# Optical_Encoder_10-17-16.net
KiCad netlist of a schematic drawn in EAGLE
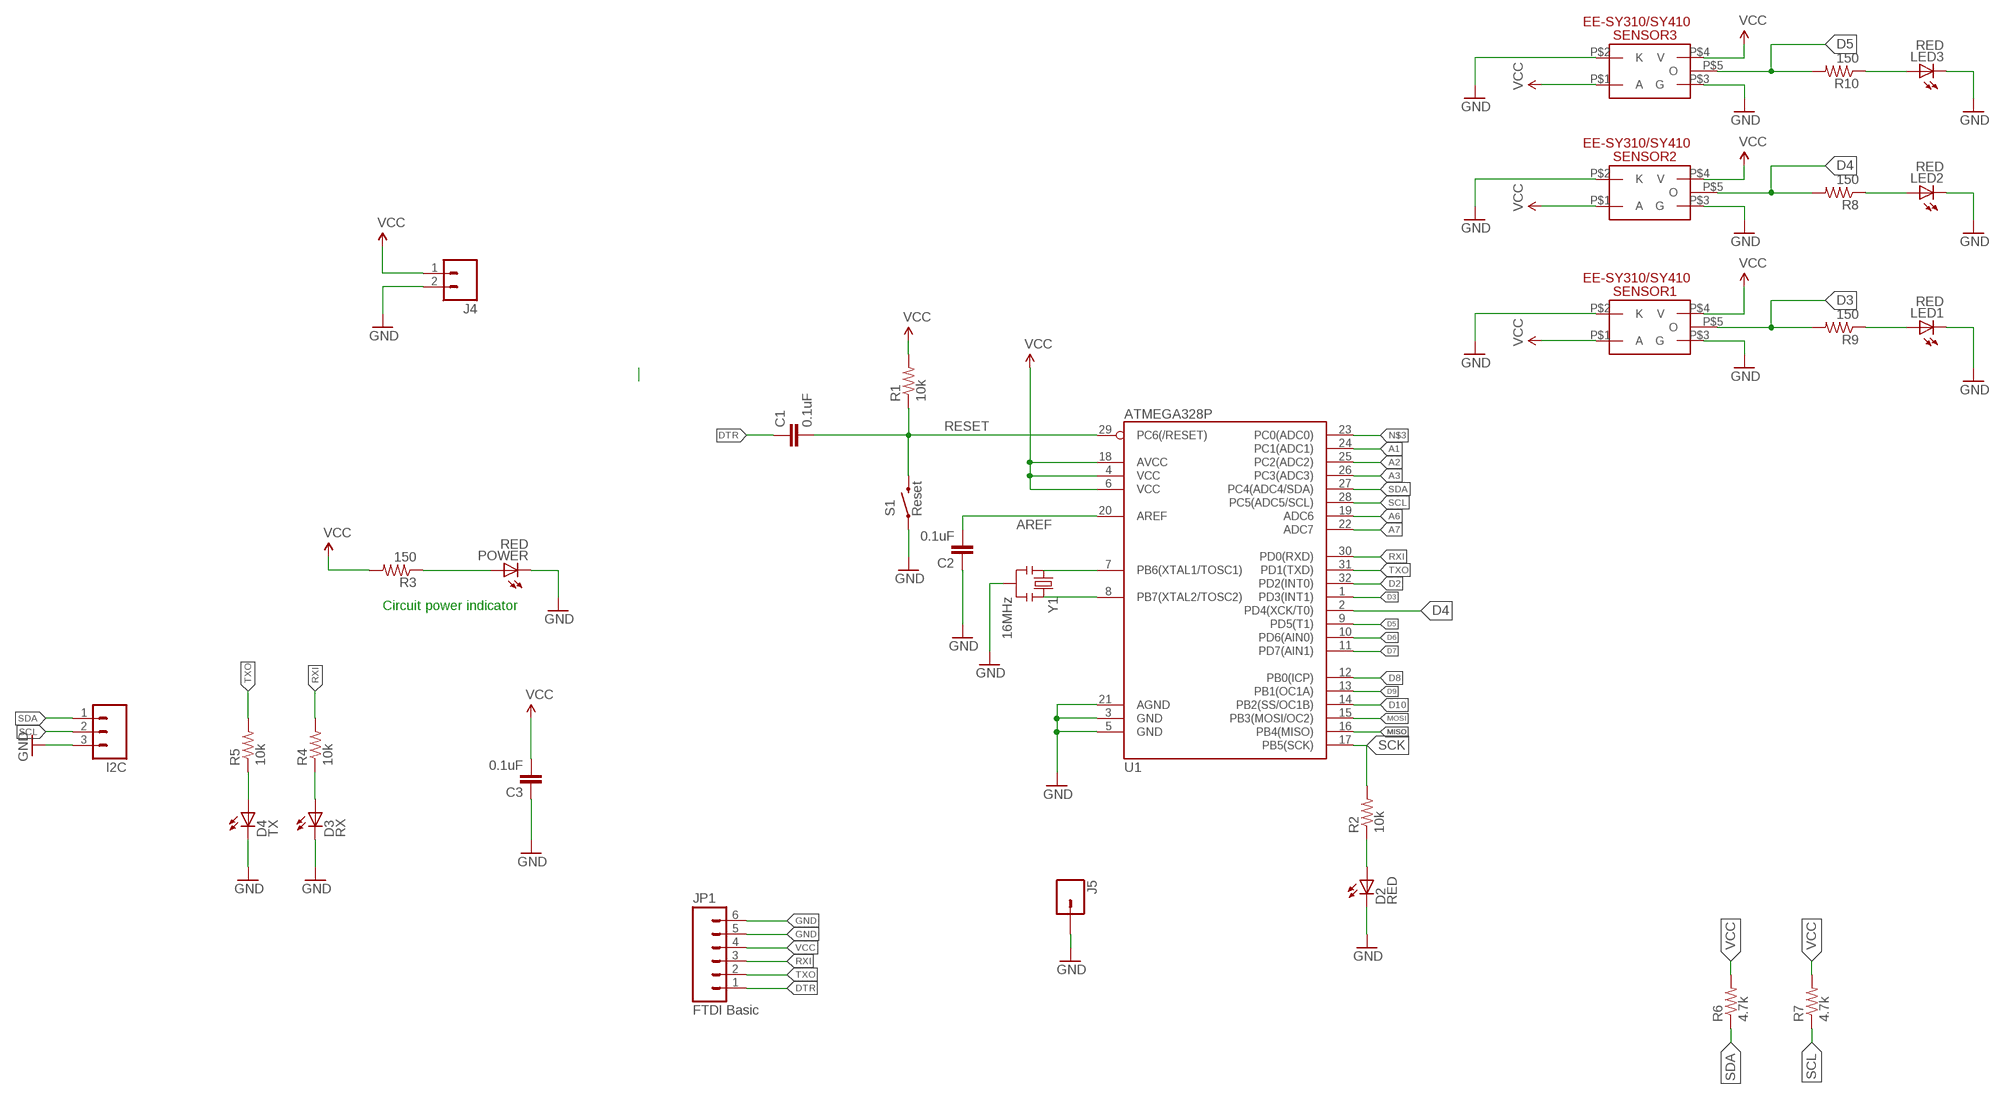
[diagram p0: schematic, sheet 1]

(export (version "E")
  (design (tool "Eeschema 10.0.6"))
  (components
    (comp (ref "C1")
      (value "0.1uF")
      (footprint "eagle-import:0603-CAP")
      (libsource (lib "eagle-import") (part "CAP0603-CAP"))
    )
    (comp (ref "C2")
      (value "0.1uF")
      (footprint "eagle-import:0603-CAP")
      (libsource (lib "eagle-import") (part "CAP0603-CAP"))
    )
    (comp (ref "C3")
      (value "0.1uF")
      (footprint "eagle-import:0603-CAP")
      (libsource (lib "eagle-import") (part "CAP0603-CAP"))
    )
    (comp (ref "D2")
      (value "RED")
      (footprint "eagle-import:LED-0603")
      (libsource (lib "eagle-import") (part "LED-RED0603"))
    )
    (comp (ref "D3")
      (value "RX")
      (footprint "eagle-import:LED-0603")
      (libsource (lib "eagle-import") (part "LED-GREEN0603"))
    )
    (comp (ref "D4")
      (value "TX")
      (footprint "eagle-import:LED-0603")
      (libsource (lib "eagle-import") (part "LED-RED0603"))
    )
    (comp (ref "I2C")
      (value "M03PTH")
      (footprint "eagle-import:1X03")
      (libsource (lib "eagle-import") (part "M03PTH"))
    )
    (comp (ref "J4")
      (value "M02PTH")
      (footprint "eagle-import:1X02")
      (libsource (lib "eagle-import") (part "M02PTH"))
    )
    (comp (ref "J5")
      (value "M01PTH")
      (footprint "eagle-import:1X01")
      (libsource (lib "eagle-import") (part "M01PTH"))
    )
    (comp (ref "JP1")
      (value "FTDI Basic")
      (footprint "eagle-import:MOLEX-1X6")
      (libsource (lib "eagle-import") (part "M06POLAR"))
    )
    (comp (ref "LED1")
      (value "RED")
      (footprint "eagle-import:LED-0603")
      (libsource (lib "eagle-import") (part "LED-RED0603"))
    )
    (comp (ref "LED2")
      (value "RED")
      (footprint "eagle-import:LED-0603")
      (libsource (lib "eagle-import") (part "LED-RED0603"))
    )
    (comp (ref "LED3")
      (value "RED")
      (footprint "eagle-import:LED-0603")
      (libsource (lib "eagle-import") (part "LED-RED0603"))
    )
    (comp (ref "POWER")
      (value "RED")
      (footprint "eagle-import:LED-0603")
      (libsource (lib "eagle-import") (part "LED-RED0603"))
    )
    (comp (ref "R1")
      (value "10k")
      (footprint "eagle-import:0603-RES")
      (libsource (lib "eagle-import") (part "RESISTOR0603-RES"))
    )
    (comp (ref "R2")
      (value "10k")
      (footprint "eagle-import:0603-RES")
      (libsource (lib "eagle-import") (part "RESISTOR0603-RES"))
    )
    (comp (ref "R3")
      (value "150")
      (footprint "eagle-import:1206")
      (libsource (lib "eagle-import") (part "SparkFun-Resistors_RESISTOR1206"))
    )
    (comp (ref "R4")
      (value "10k")
      (footprint "eagle-import:0603-RES")
      (libsource (lib "eagle-import") (part "RESISTOR0603-RES"))
    )
    (comp (ref "R5")
      (value "10k")
      (footprint "eagle-import:0603-RES")
      (libsource (lib "eagle-import") (part "RESISTOR0603-RES"))
    )
    (comp (ref "R6")
      (value "4.7k")
      (footprint "eagle-import:1206")
      (libsource (lib "eagle-import") (part "SparkFun-Resistors_RESISTOR1206"))
    )
    (comp (ref "R7")
      (value "4.7k")
      (footprint "eagle-import:1206")
      (libsource (lib "eagle-import") (part "SparkFun-Resistors_RESISTOR1206"))
    )
    (comp (ref "R8")
      (value "150")
      (footprint "eagle-import:1206")
      (libsource (lib "eagle-import") (part "SparkFun-Resistors_RESISTOR1206"))
    )
    (comp (ref "R9")
      (value "150")
      (footprint "eagle-import:1206")
      (libsource (lib "eagle-import") (part "SparkFun-Resistors_RESISTOR1206"))
    )
    (comp (ref "R10")
      (value "150")
      (footprint "eagle-import:1206")
      (libsource (lib "eagle-import") (part "SparkFun-Resistors_RESISTOR1206"))
    )
    (comp (ref "S1")
      (value "Reset")
      (footprint "eagle-import:TACTILE_SWITCH_SMD")
      (libsource (lib "eagle-import") (part "SWITCH-MOMENTARY-2SMD"))
    )
    (comp (ref "SENSOR1")
      (value "EE-SY310/SY410")
      (footprint "eagle-import:EE-SY310_SY410")
      (libsource (lib "eagle-import") (part "EE-SY310/SY410"))
    )
    (comp (ref "SENSOR2")
      (value "EE-SY310/SY410")
      (footprint "eagle-import:EE-SY310_SY410")
      (libsource (lib "eagle-import") (part "EE-SY310/SY410"))
    )
    (comp (ref "SENSOR3")
      (value "EE-SY310/SY410")
      (footprint "eagle-import:EE-SY310_SY410")
      (libsource (lib "eagle-import") (part "EE-SY310/SY410"))
    )
    (comp (ref "U1")
      (value "ATMEGA328P")
      (footprint "eagle-import:TQFP32-08")
      (libsource (lib "eagle-import") (part "ATMEGA328_SMT"))
    )
    (comp (ref "Y1")
      (value "16MHz")
      (footprint "eagle-import:RESONATOR-SMD")
      (libsource (lib "eagle-import") (part "RESONATOR16MHZ"))
    )
  )
  (nets
    (net (code "1") (name "/AREF") (class "Default")
      (node (ref "C2") (pin "2") (pinfunction "2_2") (pintype "passive"))
      (node (ref "U1") (pin "20") (pinfunction "AREF_20") (pintype "bidirectional"))
    )
    (net (code "2") (name "/RESET") (class "Default")
      (node (ref "C1") (pin "2") (pinfunction "2_2") (pintype "passive"))
      (node (ref "R1") (pin "1") (pinfunction "1_1") (pintype "passive"))
      (node (ref "S1") (pin "3") (pinfunction "2_3") (pintype "passive"))
      (node (ref "U1") (pin "29") (pinfunction "PC6(/RESET)_29") (pintype "bidirectional"))
    )
    (net (code "3") (name "A1") (class "Default")
      (node (ref "U1") (pin "24") (pinfunction "PC1(ADC1)_24") (pintype "bidirectional"))
    )
    (net (code "4") (name "A2") (class "Default")
      (node (ref "U1") (pin "25") (pinfunction "PC2(ADC2)_25") (pintype "bidirectional"))
    )
    (net (code "5") (name "A3") (class "Default")
      (node (ref "U1") (pin "26") (pinfunction "PC3(ADC3)_26") (pintype "bidirectional"))
    )
    (net (code "6") (name "A6") (class "Default")
      (node (ref "U1") (pin "19") (pinfunction "ADC6_19") (pintype "bidirectional"))
    )
    (net (code "7") (name "A7") (class "Default")
      (node (ref "U1") (pin "22") (pinfunction "ADC7_22") (pintype "bidirectional"))
    )
    (net (code "8") (name "D2") (class "Default")
      (node (ref "U1") (pin "32") (pinfunction "PD2(INT0)_32") (pintype "bidirectional"))
    )
    (net (code "9") (name "D3") (class "Default")
      (node (ref "R9") (pin "2") (pinfunction "2_2") (pintype "passive"))
      (node (ref "SENSOR1") (pin "P$5") (pinfunction "O_P$5") (pintype "bidirectional"))
      (node (ref "U1") (pin "1") (pinfunction "PD3(INT1)_1") (pintype "bidirectional"))
    )
    (net (code "10") (name "D4") (class "Default")
      (node (ref "R8") (pin "2") (pinfunction "2_2") (pintype "passive"))
      (node (ref "SENSOR2") (pin "P$5") (pinfunction "O_P$5") (pintype "bidirectional"))
      (node (ref "U1") (pin "2") (pinfunction "PD4(XCK/T0)_2") (pintype "bidirectional"))
    )
    (net (code "11") (name "D5") (class "Default")
      (node (ref "R10") (pin "2") (pinfunction "2_2") (pintype "passive"))
      (node (ref "SENSOR3") (pin "P$5") (pinfunction "O_P$5") (pintype "bidirectional"))
      (node (ref "U1") (pin "9") (pinfunction "PD5(T1)_9") (pintype "bidirectional"))
    )
    (net (code "12") (name "D6") (class "Default")
      (node (ref "U1") (pin "10") (pinfunction "PD6(AIN0)_10") (pintype "bidirectional"))
    )
    (net (code "13") (name "D7") (class "Default")
      (node (ref "U1") (pin "11") (pinfunction "PD7(AIN1)_11") (pintype "bidirectional"))
    )
    (net (code "14") (name "D8") (class "Default")
      (node (ref "U1") (pin "12") (pinfunction "PB0(ICP)_12") (pintype "bidirectional"))
    )
    (net (code "15") (name "D9") (class "Default")
      (node (ref "U1") (pin "13") (pinfunction "PB1(OC1A)_13") (pintype "bidirectional"))
    )
    (net (code "16") (name "D10") (class "Default")
      (node (ref "U1") (pin "14") (pinfunction "PB2(SS/OC1B)_14") (pintype "bidirectional"))
    )
    (net (code "17") (name "DTR") (class "Default")
      (node (ref "C1") (pin "1") (pinfunction "1_1") (pintype "passive"))
      (node (ref "JP1") (pin "1") (pinfunction "1_1") (pintype "passive"))
    )
    (net (code "18") (name "GND") (class "Default")
      (node (ref "C2") (pin "1") (pinfunction "1_1") (pintype "passive"))
      (node (ref "C3") (pin "1") (pinfunction "1_1") (pintype "passive"))
      (node (ref "D2") (pin "C") (pinfunction "C_C") (pintype "passive"))
      (node (ref "D3") (pin "C") (pinfunction "C_C") (pintype "passive"))
      (node (ref "D4") (pin "C") (pinfunction "C_C") (pintype "passive"))
      (node (ref "I2C") (pin "3") (pinfunction "3_3") (pintype "passive"))
      (node (ref "J4") (pin "2") (pinfunction "2_2") (pintype "passive"))
      (node (ref "J5") (pin "1") (pinfunction "1_1") (pintype "passive"))
      (node (ref "JP1") (pin "5") (pinfunction "5_5") (pintype "passive"))
      (node (ref "JP1") (pin "6") (pinfunction "6_6") (pintype "passive"))
      (node (ref "LED1") (pin "C") (pinfunction "C_C") (pintype "passive"))
      (node (ref "LED2") (pin "C") (pinfunction "C_C") (pintype "passive"))
      (node (ref "LED3") (pin "C") (pinfunction "C_C") (pintype "passive"))
      (node (ref "POWER") (pin "C") (pinfunction "C_C") (pintype "passive"))
      (node (ref "S1") (pin "1") (pinfunction "1_1") (pintype "passive"))
      (node (ref "SENSOR1") (pin "P$2") (pinfunction "K_P$2") (pintype "bidirectional"))
      (node (ref "SENSOR1") (pin "P$3") (pinfunction "G_P$3") (pintype "bidirectional"))
      (node (ref "SENSOR2") (pin "P$2") (pinfunction "K_P$2") (pintype "bidirectional"))
      (node (ref "SENSOR2") (pin "P$3") (pinfunction "G_P$3") (pintype "bidirectional"))
      (node (ref "SENSOR3") (pin "P$2") (pinfunction "K_P$2") (pintype "bidirectional"))
      (node (ref "SENSOR3") (pin "P$3") (pinfunction "G_P$3") (pintype "bidirectional"))
      (node (ref "U1") (pin "21") (pinfunction "AGND_21") (pintype "bidirectional"))
      (node (ref "U1") (pin "3") (pinfunction "GND_3") (pintype "bidirectional"))
      (node (ref "U1") (pin "5") (pinfunction "GND_5") (pintype "bidirectional"))
      (node (ref "Y1") (pin "2") (pinfunction "2_2") (pintype "passive"))
    )
    (net (code "19") (name "MISO") (class "Default")
      (node (ref "U1") (pin "16") (pinfunction "PB4(MISO)_16") (pintype "bidirectional"))
    )
    (net (code "20") (name "MOSI") (class "Default")
      (node (ref "U1") (pin "15") (pinfunction "PB3(MOSI/OC2)_15") (pintype "bidirectional"))
    )
    (net (code "21") (name "N$3") (class "Default")
      (node (ref "U1") (pin "23") (pinfunction "PC0(ADC0)_23") (pintype "bidirectional"))
    )
    (net (code "22") (name "Net-(D2-PadA)") (class "Default")
      (node (ref "D2") (pin "A") (pinfunction "A_A") (pintype "passive"))
      (node (ref "R2") (pin "1") (pinfunction "1_1") (pintype "passive"))
    )
    (net (code "23") (name "Net-(D3-PadA)") (class "Default")
      (node (ref "D3") (pin "A") (pinfunction "A_A") (pintype "passive"))
      (node (ref "R4") (pin "1") (pinfunction "1_1") (pintype "passive"))
    )
    (net (code "24") (name "Net-(D4-PadA)") (class "Default")
      (node (ref "D4") (pin "A") (pinfunction "A_A") (pintype "passive"))
      (node (ref "R5") (pin "1") (pinfunction "1_1") (pintype "passive"))
    )
    (net (code "25") (name "Net-(LED1-PadA)") (class "Default")
      (node (ref "LED1") (pin "A") (pinfunction "A_A") (pintype "passive"))
      (node (ref "R9") (pin "1") (pinfunction "1_1") (pintype "passive"))
    )
    (net (code "26") (name "Net-(LED2-PadA)") (class "Default")
      (node (ref "LED2") (pin "A") (pinfunction "A_A") (pintype "passive"))
      (node (ref "R8") (pin "1") (pinfunction "1_1") (pintype "passive"))
    )
    (net (code "27") (name "Net-(LED3-PadA)") (class "Default")
      (node (ref "LED3") (pin "A") (pinfunction "A_A") (pintype "passive"))
      (node (ref "R10") (pin "1") (pinfunction "1_1") (pintype "passive"))
    )
    (net (code "28") (name "Net-(POWER-PadA)") (class "Default")
      (node (ref "POWER") (pin "A") (pinfunction "A_A") (pintype "passive"))
      (node (ref "R3") (pin "1") (pinfunction "1_1") (pintype "passive"))
    )
    (net (code "29") (name "Net-(U1-PB6(XTAL1{slash}TOSC1))") (class "Default")
      (node (ref "U1") (pin "7") (pinfunction "PB6(XTAL1/TOSC1)_7") (pintype "bidirectional"))
      (node (ref "Y1") (pin "1") (pinfunction "1_1") (pintype "passive"))
    )
    (net (code "30") (name "Net-(U1-PB7(XTAL2{slash}TOSC2))") (class "Default")
      (node (ref "U1") (pin "8") (pinfunction "PB7(XTAL2/TOSC2)_8") (pintype "bidirectional"))
      (node (ref "Y1") (pin "3") (pinfunction "3_3") (pintype "passive"))
    )
    (net (code "31") (name "RXI") (class "Default")
      (node (ref "JP1") (pin "3") (pinfunction "3_3") (pintype "passive"))
      (node (ref "R4") (pin "2") (pinfunction "2_2") (pintype "passive"))
      (node (ref "U1") (pin "30") (pinfunction "PD0(RXD)_30") (pintype "bidirectional"))
    )
    (net (code "32") (name "SCK") (class "Default")
      (node (ref "R2") (pin "2") (pinfunction "2_2") (pintype "passive"))
      (node (ref "U1") (pin "17") (pinfunction "PB5(SCK)_17") (pintype "bidirectional"))
    )
    (net (code "33") (name "SCL") (class "Default")
      (node (ref "I2C") (pin "2") (pinfunction "2_2") (pintype "passive"))
      (node (ref "R7") (pin "1") (pinfunction "1_1") (pintype "passive"))
      (node (ref "U1") (pin "28") (pinfunction "PC5(ADC5/SCL)_28") (pintype "bidirectional"))
    )
    (net (code "34") (name "SDA") (class "Default")
      (node (ref "I2C") (pin "1") (pinfunction "1_1") (pintype "passive"))
      (node (ref "R6") (pin "1") (pinfunction "1_1") (pintype "passive"))
      (node (ref "U1") (pin "27") (pinfunction "PC4(ADC4/SDA)_27") (pintype "bidirectional"))
    )
    (net (code "35") (name "TXO") (class "Default")
      (node (ref "JP1") (pin "2") (pinfunction "2_2") (pintype "passive"))
      (node (ref "R5") (pin "2") (pinfunction "2_2") (pintype "passive"))
      (node (ref "U1") (pin "31") (pinfunction "PD1(TXD)_31") (pintype "bidirectional"))
    )
    (net (code "36") (name "VCC") (class "Default")
      (node (ref "C3") (pin "2") (pinfunction "2_2") (pintype "passive"))
      (node (ref "J4") (pin "1") (pinfunction "1_1") (pintype "passive"))
      (node (ref "JP1") (pin "4") (pinfunction "4_4") (pintype "passive"))
      (node (ref "R1") (pin "2") (pinfunction "2_2") (pintype "passive"))
      (node (ref "R3") (pin "2") (pinfunction "2_2") (pintype "passive"))
      (node (ref "R6") (pin "2") (pinfunction "2_2") (pintype "passive"))
      (node (ref "R7") (pin "2") (pinfunction "2_2") (pintype "passive"))
      (node (ref "SENSOR1") (pin "P$1") (pinfunction "A_P$1") (pintype "bidirectional"))
      (node (ref "SENSOR1") (pin "P$4") (pinfunction "V_P$4") (pintype "bidirectional"))
      (node (ref "SENSOR2") (pin "P$1") (pinfunction "A_P$1") (pintype "bidirectional"))
      (node (ref "SENSOR2") (pin "P$4") (pinfunction "V_P$4") (pintype "bidirectional"))
      (node (ref "SENSOR3") (pin "P$1") (pinfunction "A_P$1") (pintype "bidirectional"))
      (node (ref "SENSOR3") (pin "P$4") (pinfunction "V_P$4") (pintype "bidirectional"))
      (node (ref "U1") (pin "18") (pinfunction "AVCC_18") (pintype "bidirectional"))
      (node (ref "U1") (pin "4") (pinfunction "VCC_4") (pintype "bidirectional"))
      (node (ref "U1") (pin "6") (pinfunction "VCC_6") (pintype "bidirectional"))
    )
  )
)
